# tinyCurrent_Version1.net
KiCad netlist of a schematic drawn in Altium Designer
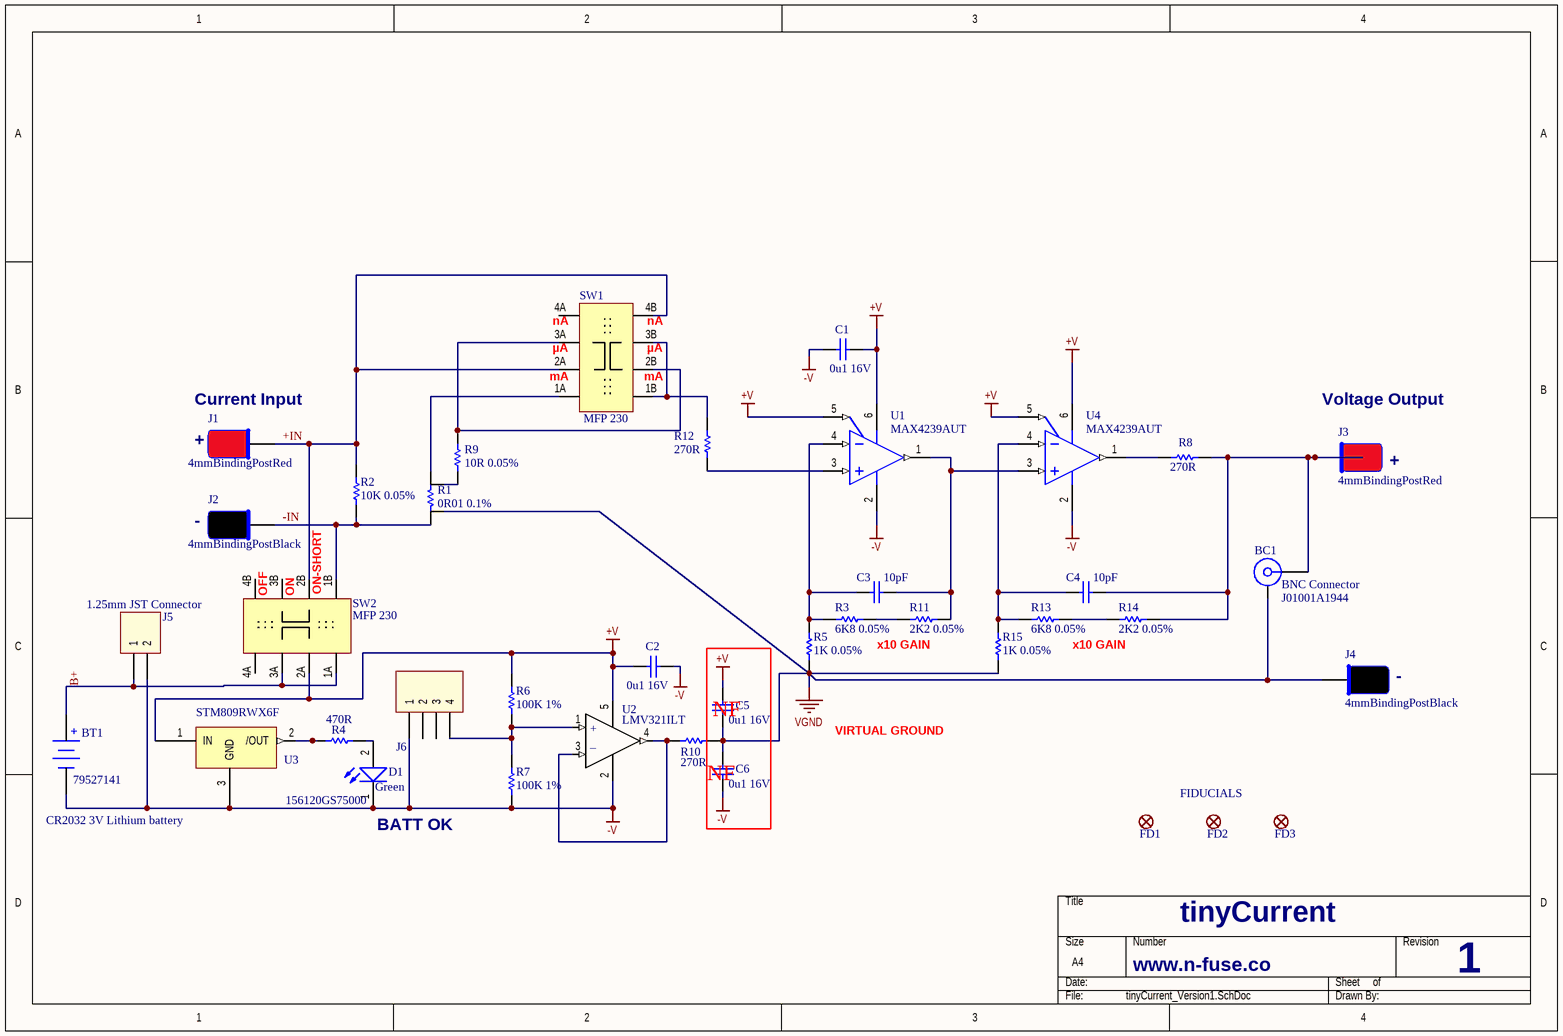
[diagram p0: tinyCurrent_Version1.SchDoc]

(export (version "E")
  (design (tool "Eeschema 10.0.6"))
  (components
    (comp (ref "BC1")
      (value "J01001A1944")
      (footprint "ROS-51K101-400A4_V")
      (description "BNC 50R Straight Jack, Up to 10 GHz, -55 to 155 degC")
      (fields (field (name "PARTNUMBER") "51K101-400A4"))
      (libsource (lib "tinyCurrent_Version1") (part "51K101-400A4"))
    )
    (comp (ref "BT1")
      (value "79527141")
      (footprint "79527141")
      (description "Battery Holder WA-BCPH, Battery Type: 2032p")
      (fields (field (name "PUBLISHER") "Wurth Elektronik"))
      (libsource (lib "ALTIUM-BCPH_BATTERY_HOLDER-rev16a") (part "79527141"))
    )
    (comp (ref "C1")
      (value "0u1 16V")
      (footprint "WCAP-CSGP_0603, 1.6x0.8x0.8")
      (description "WCAP-CSGP Ceramic Capacitors, 0603, 100000pF")
      (fields (field (name "PARTNUMBER") "885012206046") (field (name "PUBLISHER") "Wurth Elektronik"))
      (libsource (lib "ALTIUM-WCAP-CSGP-0603-rev16a (1)") (part "WCAP-CSGP, 885012206046"))
    )
    (comp (ref "C2")
      (value "0u1 16V")
      (footprint "WCAP-CSGP_0603, 1.6x0.8x0.8")
      (description "WCAP-CSGP Ceramic Capacitors, 0603, 100000pF")
      (fields (field (name "PARTNUMBER") "885012206046") (field (name "PUBLISHER") "Wurth Elektronik"))
      (libsource (lib "ALTIUM-WCAP-CSGP-0603-rev16a (1)") (part "WCAP-CSGP, 885012206046"))
    )
    (comp (ref "C3")
      (value "10pF")
      (footprint "WCAP-CSGP_0603, 1.6x0.8x0.8")
      (description "WCAP-CSGP Ceramic Capacitors, 0603, 10pF")
      (fields (field (name "PARTNUMBER") "885012006051") (field (name "PUBLISHER") "Wurth Elektronik"))
      (libsource (lib "ALTIUM-WCAP-CSGP-0603-rev16a (1)") (part "WCAP-CSGP, 885012006051"))
    )
    (comp (ref "C4")
      (value "10pF")
      (footprint "WCAP-CSGP_0603, 1.6x0.8x0.8")
      (description "WCAP-CSGP Ceramic Capacitors, 0603, 10pF")
      (fields (field (name "PARTNUMBER") "885012006051") (field (name "PUBLISHER") "Wurth Elektronik"))
      (libsource (lib "ALTIUM-WCAP-CSGP-0603-rev16a (1)") (part "WCAP-CSGP, 885012006051"))
    )
    (comp (ref "C5")
      (value "0u1 16V")
      (footprint "WCAP-CSGP_0603, 1.6x0.8x0.8")
      (description "WCAP-CSGP Ceramic Capacitors, 0603, 100000pF")
      (fields (field (name "PARTNUMBER") "885012206046") (field (name "PUBLISHER") "Wurth Elektronik"))
      (libsource (lib "tinyCurrent_Version1") (part "WCAP-CSGP, 885012206046"))
    )
    (comp (ref "C6")
      (value "0u1 16V")
      (footprint "WCAP-CSGP_0603, 1.6x0.8x0.8")
      (description "WCAP-CSGP Ceramic Capacitors, 0603, 100000pF")
      (fields (field (name "PARTNUMBER") "885012206046") (field (name "PUBLISHER") "Wurth Elektronik"))
      (libsource (lib "tinyCurrent_Version1") (part "WCAP-CSGP, 885012206046"))
    )
    (comp (ref "D1")
      (value "156120GS75000")
      (footprint "WL-SMRW_1206 rectangular_Normal use")
      (description "WL-SMRW SMD Mono-color Reverse mount Waterclear, size 1206 rectangular, Green")
      (fields (field (name "EMITTINGCOLOR") "Green") (field (name "PUBLISHER") "Wurth Elektronik"))
      (libsource (lib "ALTIUM-WL-SMRW-rev17a") (part "156120GS75000"))
    )
    (comp (ref "FD1")
      (value "FIDUCIAL1X2")
      (footprint "FIDUCIAL-1X2")
      (libsource (lib "SBCPoE BBB") (part "FIDUCIAL1X2"))
    )
    (comp (ref "FD2")
      (value "FIDUCIAL1X2")
      (footprint "FIDUCIAL-1X2")
      (libsource (lib "SBCPoE BBB") (part "FIDUCIAL1X2"))
    )
    (comp (ref "FD3")
      (value "FIDUCIAL1X2")
      (footprint "FIDUCIAL-1X2")
      (libsource (lib "SBCPoE BBB") (part "FIDUCIAL1X2"))
    )
    (comp (ref "J1")
      (value "4mmBindingPostRed")
      (footprint "4mmBindingPost")
      (libsource (lib "tinyCurrent_Version1") (part "4mmBindingPostRed"))
    )
    (comp (ref "J2")
      (value "4mmBindingPostBlack")
      (footprint "4mmBindingPost")
      (libsource (lib "tinyCurrent_Version1") (part "4mmBindingPostBlack"))
    )
    (comp (ref "J3")
      (value "4mmBindingPostRed")
      (footprint "4mmBindingPost")
      (libsource (lib "tinyCurrent_Version1") (part "4mmBindingPostRed"))
    )
    (comp (ref "J4")
      (value "4mmBindingPostBlack")
      (footprint "4mmBindingPost")
      (libsource (lib "tinyCurrent_Version1") (part "4mmBindingPostBlack"))
    )
    (comp (ref "J5")
      (value "1.25mm JST Connector")
      (footprint "653102131822")
      (description "WR-WTB 1.25mm SMT Male Horizontal Shrouded Header, 2p")
      (fields (field (name "PART NUMBER") "653102131822") (field (name "PUBLISHER") "Wurth Elektronik"))
      (libsource (lib "ALTIUM-WTB_1_25_SMT_MALE_HORIZONTAL_SHROUDED_HEADER_6531XX131822-rev17a") (part "653102131822"))
    )
    (comp (ref "J6")
      (value "61000413321")
      (footprint "61000413321")
      (description "WR-PHD 2.54 mm SMT Socket Header, 4p")
      (fields (field (name "PUBLISHER") "Wurth Elektronik"))
      (libsource (lib "ALTIUM-PHD_2_54_SMT_SOCKET_HEADER_6100XXXXX21-rev17a") (part "61000413321"))
    )
    (comp (ref "R1")
      (value "0R01 0.1%")
      (footprint "2512shuntresistor")
      (description "1206 Current Shunt")
      (libsource (lib "uCurrent") (part "1206currentShunt"))
    )
    (comp (ref "R2")
      (value "10K 0.05%")
      (footprint "RESC1608N")
      (fields (field (name "TOLERANCE") "1 %"))
      (libsource (lib "AltiumDesignLibrary") (part "RES"))
    )
    (comp (ref "R3")
      (value "6K8 0.05%")
      (footprint "RESC1608N")
      (fields (field (name "TOLERANCE") "1 %"))
      (libsource (lib "AltiumDesignLibrary") (part "RES"))
    )
    (comp (ref "R4")
      (value "470R")
      (footprint "RESC1608N")
      (fields (field (name "TOLERANCE") "1 %"))
      (libsource (lib "AltiumDesignLibrary") (part "RES"))
    )
    (comp (ref "R5")
      (value "1K 0.05%")
      (footprint "RESC1608N")
      (fields (field (name "TOLERANCE") "1 %"))
      (libsource (lib "AltiumDesignLibrary") (part "RES"))
    )
    (comp (ref "R6")
      (value "100K 1%")
      (footprint "RESC1608N")
      (fields (field (name "TOLERANCE") "1 %"))
      (libsource (lib "AltiumDesignLibrary") (part "RES"))
    )
    (comp (ref "R7")
      (value "100K 1%")
      (footprint "RESC1608N")
      (fields (field (name "TOLERANCE") "1 %"))
      (libsource (lib "AltiumDesignLibrary") (part "RES"))
    )
    (comp (ref "R8")
      (value "270R")
      (footprint "RESC1608N")
      (fields (field (name "TOLERANCE") "1 %"))
      (libsource (lib "AltiumDesignLibrary") (part "RES"))
    )
    (comp (ref "R9")
      (value "10R 0.05%")
      (footprint "RESC2012N")
      (fields (field (name "TOLERANCE") "1 %"))
      (libsource (lib "AltiumDesignLibrary") (part "RES"))
    )
    (comp (ref "R10")
      (value "270R")
      (footprint "RESC1608N")
      (fields (field (name "TOLERANCE") "1 %"))
      (libsource (lib "AltiumDesignLibrary") (part "RES"))
    )
    (comp (ref "R11")
      (value "2K2 0.05%")
      (footprint "RESC1608N")
      (fields (field (name "TOLERANCE") "1 %"))
      (libsource (lib "AltiumDesignLibrary") (part "RES"))
    )
    (comp (ref "R12")
      (value "270R")
      (footprint "RESC1608N")
      (fields (field (name "TOLERANCE") "1 %"))
      (libsource (lib "AltiumDesignLibrary") (part "RES"))
    )
    (comp (ref "R13")
      (value "6K8 0.05%")
      (footprint "RESC1608N")
      (fields (field (name "TOLERANCE") "1 %"))
      (libsource (lib "AltiumDesignLibrary") (part "RES"))
    )
    (comp (ref "R14")
      (value "2K2 0.05%")
      (footprint "RESC1608N")
      (fields (field (name "TOLERANCE") "1 %"))
      (libsource (lib "AltiumDesignLibrary") (part "RES"))
    )
    (comp (ref "R15")
      (value "1K 0.05%")
      (footprint "RESC1608N")
      (fields (field (name "TOLERANCE") "1 %"))
      (libsource (lib "AltiumDesignLibrary") (part "RES"))
    )
    (comp (ref "SW1")
      (value "MFP 230")
      (footprint "KnitterSideSwitch:MFP 230")
      (description "Slide Switch")
      (libsource (lib "") (part "MFP 230_1"))
    )
    (comp (ref "SW2")
      (value "MFP 230")
      (footprint "KnitterSideSwitch:MFP 230")
      (description "Slide Switch")
      (libsource (lib "tinyCurrent_Version1") (part "MFP 230"))
    )
    (comp (ref "U1")
      (value "MAX4239AUT")
      (footprint "SOT-23-CH6_N")
      (fields (field (name "PUBLISHER") "Altium Limited"))
      (libsource (lib "CurrentRev5") (part "MCP6273T-E/CH"))
    )
    (comp (ref "U2")
      (value "LMV321ILT")
      (footprint "SOT95P280X130-5N")
      (libsource (lib "uCurrentnf_Version1") (part "Component_1_1"))
    )
    (comp (ref "U3")
      (value "STM809RWX6F")
      (footprint "SOT23")
      (libsource (lib "uCurrent") (part "VoltageSupervisor"))
    )
    (comp (ref "U4")
      (value "MAX4239AUT")
      (footprint "SOT-23-CH6_N")
      (fields (field (name "PUBLISHER") "Altium Limited"))
      (libsource (lib "CurrentRev5") (part "MCP6273T-E/CH"))
    )
  )
  (nets
    (net (code "1") (name "+V") (class "Default")
      (node (ref "C1") (pin "2") (pinfunction "2_2") (pintype "passive"))
      (node (ref "C2") (pin "1") (pinfunction "1_1") (pintype "passive"))
      (node (ref "C5") (pin "2") (pinfunction "2_2") (pintype "passive"))
      (node (ref "R6") (pin "2") (pinfunction "2_2") (pintype "passive"))
      (node (ref "SW2") (pin "2A") (pinfunction "2A_2A") (pintype "passive"))
      (node (ref "U1") (pin "5") (pinfunction "~{CS}_5") (pintype "input"))
      (node (ref "U1") (pin "6") (pinfunction "VDD_6") (pintype "power_in"))
      (node (ref "U2") (pin "5") (pinfunction "5_5") (pintype "power_in"))
      (node (ref "U3") (pin "1") (pinfunction "IN_1") (pintype "power_in"))
      (node (ref "U4") (pin "5") (pinfunction "~{CS}_5") (pintype "input"))
      (node (ref "U4") (pin "6") (pinfunction "VDD_6") (pintype "power_in"))
    )
    (net (code "2") (name "-V") (class "Default")
      (node (ref "BT1") (pin "2") (pinfunction "Neg_2") (pintype "passive"))
      (node (ref "C1") (pin "1") (pinfunction "1_1") (pintype "passive"))
      (node (ref "C2") (pin "2") (pinfunction "2_2") (pintype "passive"))
      (node (ref "C6") (pin "1") (pinfunction "1_1") (pintype "passive"))
      (node (ref "D1") (pin "1") (pinfunction "K_1") (pintype "passive"))
      (node (ref "J5") (pin "2") (pinfunction "2_2") (pintype "passive"))
      (node (ref "J6") (pin "1") (pinfunction "1_1") (pintype "passive"))
      (node (ref "R7") (pin "2") (pinfunction "2_2") (pintype "passive"))
      (node (ref "U1") (pin "2") (pinfunction "VSS_2") (pintype "power_in"))
      (node (ref "U2") (pin "2") (pinfunction "2_2") (pintype "power_in"))
      (node (ref "U3") (pin "3") (pinfunction "GND_3") (pintype "power_in"))
      (node (ref "U4") (pin "2") (pinfunction "VSS_2") (pintype "power_in"))
    )
    (net (code "3") (name "/+IN") (class "Default")
      (node (ref "J1") (pin "1") (pinfunction "NOISE_1") (pintype "passive"))
      (node (ref "R2") (pin "1") (pinfunction "1_1") (pintype "passive"))
      (node (ref "SW1") (pin "2A") (pinfunction "2A_2A") (pintype "passive"))
      (node (ref "SW1") (pin "4B") (pinfunction "4B_4B") (pintype "passive"))
      (node (ref "SW2") (pin "2B") (pinfunction "2B_2B") (pintype "passive"))
    )
    (net (code "4") (name "/-IN") (class "Default")
      (node (ref "J2") (pin "1") (pinfunction "NOISE_1") (pintype "passive"))
      (node (ref "R1") (pin "2") (pinfunction "2_2") (pintype "passive"))
      (node (ref "R2") (pin "2") (pinfunction "2_2") (pintype "passive"))
      (node (ref "SW2") (pin "1B") (pinfunction "1B_1B") (pintype "passive"))
    )
    (net (code "5") (name "/B+") (class "Default")
      (node (ref "BT1") (pin "1") (pinfunction "Pos_1") (pintype "passive"))
      (node (ref "J5") (pin "1") (pinfunction "1_1") (pintype "passive"))
      (node (ref "SW2") (pin "1A") (pinfunction "1A_1A") (pintype "passive"))
      (node (ref "SW2") (pin "3A") (pinfunction "3A_3A") (pintype "passive"))
    )
    (net (code "6") (name "Net-(D1-A)") (class "Default")
      (node (ref "D1") (pin "2") (pinfunction "A_2") (pintype "passive"))
      (node (ref "R4") (pin "1") (pinfunction "1_1") (pintype "passive"))
    )
    (net (code "7") (name "Net-(J3-NOISE)") (class "Default")
      (node (ref "BC1") (pin "1") (pinfunction "1_1") (pintype "passive"))
      (node (ref "C4") (pin "2") (pinfunction "2_2") (pintype "passive"))
      (node (ref "J3") (pin "1") (pinfunction "NOISE_1") (pintype "passive"))
      (node (ref "R14") (pin "2") (pinfunction "2_2") (pintype "passive"))
      (node (ref "R8") (pin "1") (pinfunction "1_1") (pintype "passive"))
    )
    (net (code "8") (name "Net-(J6-Pad4)") (class "Default")
      (node (ref "J6") (pin "4") (pinfunction "4_4") (pintype "passive"))
      (node (ref "R6") (pin "1") (pinfunction "1_1") (pintype "passive"))
      (node (ref "R7") (pin "1") (pinfunction "1_1") (pintype "passive"))
      (node (ref "U2") (pin "1") (pinfunction "1_1") (pintype "input"))
    )
    (net (code "9") (name "Net-(R1-Pad1)") (class "Default")
      (node (ref "R1") (pin "1") (pinfunction "1_1") (pintype "passive"))
      (node (ref "SW1") (pin "1A") (pinfunction "1A_1A") (pintype "passive"))
    )
    (net (code "10") (name "Net-(R1-Pad3)") (class "Default")
      (node (ref "R1") (pin "3") (pinfunction "3_3") (pintype "passive"))
      (node (ref "R9") (pin "2") (pinfunction "2_2") (pintype "passive"))
    )
    (net (code "11") (name "Net-(R9-Pad1)") (class "Default")
      (node (ref "R9") (pin "1") (pinfunction "1_1") (pintype "passive"))
      (node (ref "SW1") (pin "2B") (pinfunction "2B_2B") (pintype "passive"))
      (node (ref "SW1") (pin "3A") (pinfunction "3A_3A") (pintype "passive"))
    )
    (net (code "12") (name "Net-(R10-Pad2)") (class "Default")
      (node (ref "R10") (pin "2") (pinfunction "2_2") (pintype "passive"))
      (node (ref "U2") (pin "3") (pinfunction "3_3") (pintype "input"))
      (node (ref "U2") (pin "4") (pinfunction "4_4") (pintype "output"))
    )
    (net (code "13") (name "Net-(R11-Pad1)") (class "Default")
      (node (ref "R11") (pin "1") (pinfunction "1_1") (pintype "passive"))
      (node (ref "R3") (pin "2") (pinfunction "2_2") (pintype "passive"))
    )
    (net (code "14") (name "Net-(R12-Pad1)") (class "Default")
      (node (ref "R12") (pin "1") (pinfunction "1_1") (pintype "passive"))
      (node (ref "SW1") (pin "1B") (pinfunction "1B_1B") (pintype "passive"))
      (node (ref "SW1") (pin "3B") (pinfunction "3B_3B") (pintype "passive"))
    )
    (net (code "15") (name "Net-(R13-Pad2)") (class "Default")
      (node (ref "R13") (pin "2") (pinfunction "2_2") (pintype "passive"))
      (node (ref "R14") (pin "1") (pinfunction "1_1") (pintype "passive"))
    )
    (net (code "16") (name "Net-(U1-VIN+)") (class "Default")
      (node (ref "R12") (pin "2") (pinfunction "2_2") (pintype "passive"))
      (node (ref "U1") (pin "3") (pinfunction "VIN+_3") (pintype "input"))
    )
    (net (code "17") (name "Net-(U1-VIN-)") (class "Default")
      (node (ref "C3") (pin "1") (pinfunction "1_1") (pintype "passive"))
      (node (ref "R3") (pin "1") (pinfunction "1_1") (pintype "passive"))
      (node (ref "R5") (pin "1") (pinfunction "1_1") (pintype "passive"))
      (node (ref "U1") (pin "4") (pinfunction "VIN-_4") (pintype "input"))
    )
    (net (code "18") (name "Net-(U1-VOUT)") (class "Default")
      (node (ref "C3") (pin "2") (pinfunction "2_2") (pintype "passive"))
      (node (ref "R11") (pin "2") (pinfunction "2_2") (pintype "passive"))
      (node (ref "U1") (pin "1") (pinfunction "VOUT_1") (pintype "output"))
      (node (ref "U4") (pin "3") (pinfunction "VIN+_3") (pintype "input"))
    )
    (net (code "19") (name "Net-(U3-{slash}OUT)") (class "Default")
      (node (ref "R4") (pin "2") (pinfunction "2_2") (pintype "passive"))
      (node (ref "U3") (pin "2") (pinfunction "/OUT_2") (pintype "output"))
    )
    (net (code "20") (name "Net-(U4-VIN-)") (class "Default")
      (node (ref "C4") (pin "1") (pinfunction "1_1") (pintype "passive"))
      (node (ref "R13") (pin "1") (pinfunction "1_1") (pintype "passive"))
      (node (ref "R15") (pin "1") (pinfunction "1_1") (pintype "passive"))
      (node (ref "U4") (pin "4") (pinfunction "VIN-_4") (pintype "input"))
    )
    (net (code "21") (name "Net-(U4-VOUT)") (class "Default")
      (node (ref "R8") (pin "2") (pinfunction "2_2") (pintype "passive"))
      (node (ref "U4") (pin "1") (pinfunction "VOUT_1") (pintype "output"))
    )
    (net (code "22") (name "VGND") (class "Default")
      (node (ref "BC1") (pin "MH") (pinfunction "MH_MH") (pintype "passive"))
      (node (ref "C5") (pin "1") (pinfunction "1_1") (pintype "passive"))
      (node (ref "C6") (pin "2") (pinfunction "2_2") (pintype "passive"))
      (node (ref "J4") (pin "1") (pinfunction "NOISE_1") (pintype "passive"))
      (node (ref "R1") (pin "4") (pinfunction "4_4") (pintype "passive"))
      (node (ref "R10") (pin "1") (pinfunction "1_1") (pintype "passive"))
      (node (ref "R15") (pin "2") (pinfunction "2_2") (pintype "passive"))
      (node (ref "R5") (pin "2") (pinfunction "2_2") (pintype "passive"))
    )
    (net (code "23") (name "unconnected-(J6-Pad2)") (class "Default")
      (node (ref "J6") (pin "2") (pinfunction "2_2") (pintype "passive"))
    )
    (net (code "24") (name "unconnected-(J6-Pad3)") (class "Default")
      (node (ref "J6") (pin "3") (pinfunction "3_3") (pintype "passive"))
    )
    (net (code "25") (name "unconnected-(SW1-Pad4A)") (class "Default")
      (node (ref "SW1") (pin "4A") (pinfunction "4A_4A") (pintype "passive"))
    )
    (net (code "26") (name "unconnected-(SW2-Pad3B)") (class "Default")
      (node (ref "SW2") (pin "3B") (pinfunction "3B_3B") (pintype "passive"))
    )
    (net (code "27") (name "unconnected-(SW2-Pad4A)") (class "Default")
      (node (ref "SW2") (pin "4A") (pinfunction "4A_4A") (pintype "passive"))
    )
    (net (code "28") (name "unconnected-(SW2-Pad4B)") (class "Default")
      (node (ref "SW2") (pin "4B") (pinfunction "4B_4B") (pintype "passive"))
    )
  )
)
